# M7101.net
KiCad netlist of a schematic drawn in EAGLE
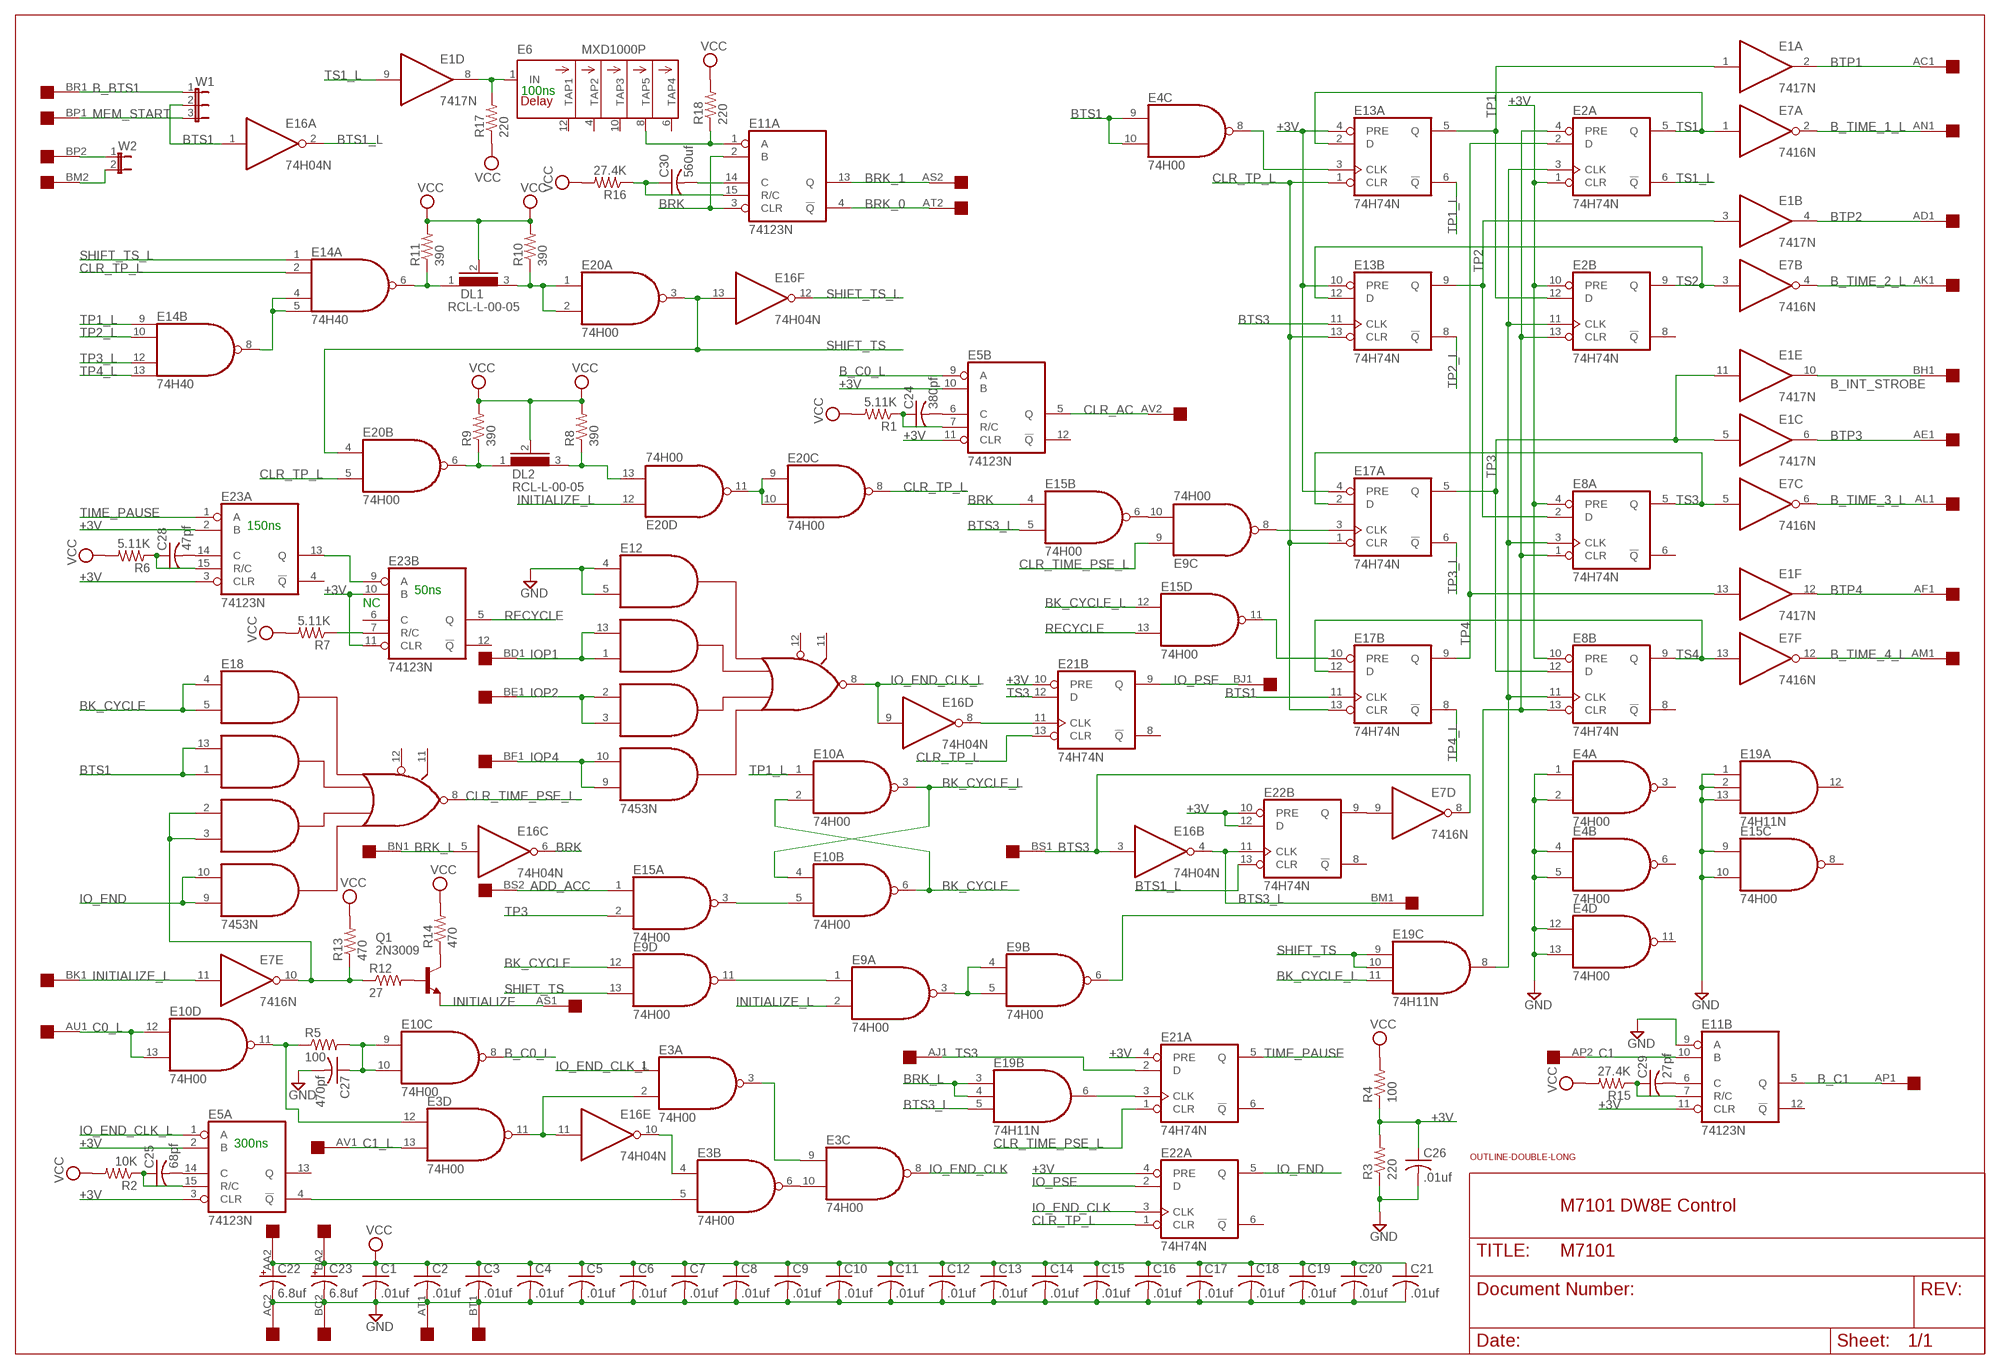
[diagram p0: schematic, sheet 1]

(export (version "E")
  (design (tool "Eeschema 10.0.6"))
  (components
    (comp (ref "C1")
      (value ".01uf")
      (footprint "eagle-import:C050-025X075")
      (libsource (lib "eagle-import") (part "C-US050-025X075"))
    )
    (comp (ref "C2")
      (value ".01uf")
      (footprint "eagle-import:C050-025X075")
      (libsource (lib "eagle-import") (part "C-US050-025X075"))
    )
    (comp (ref "C3")
      (value ".01uf")
      (footprint "eagle-import:C050-025X075")
      (libsource (lib "eagle-import") (part "C-US050-025X075"))
    )
    (comp (ref "C4")
      (value ".01uf")
      (footprint "eagle-import:C050-025X075")
      (libsource (lib "eagle-import") (part "C-US050-025X075"))
    )
    (comp (ref "C5")
      (value ".01uf")
      (footprint "eagle-import:C050-025X075")
      (libsource (lib "eagle-import") (part "C-US050-025X075"))
    )
    (comp (ref "C6")
      (value ".01uf")
      (footprint "eagle-import:C050-025X075")
      (libsource (lib "eagle-import") (part "C-US050-025X075"))
    )
    (comp (ref "C7")
      (value ".01uf")
      (footprint "eagle-import:C050-025X075")
      (libsource (lib "eagle-import") (part "C-US050-025X075"))
    )
    (comp (ref "C8")
      (value ".01uf")
      (footprint "eagle-import:C050-025X075")
      (libsource (lib "eagle-import") (part "C-US050-025X075"))
    )
    (comp (ref "C9")
      (value ".01uf")
      (footprint "eagle-import:C050-025X075")
      (libsource (lib "eagle-import") (part "C-US050-025X075"))
    )
    (comp (ref "C10")
      (value ".01uf")
      (footprint "eagle-import:C050-025X075")
      (libsource (lib "eagle-import") (part "C-US050-025X075"))
    )
    (comp (ref "C11")
      (value ".01uf")
      (footprint "eagle-import:C050-025X075")
      (libsource (lib "eagle-import") (part "C-US050-025X075"))
    )
    (comp (ref "C12")
      (value ".01uf")
      (footprint "eagle-import:C050-025X075")
      (libsource (lib "eagle-import") (part "C-US050-025X075"))
    )
    (comp (ref "C13")
      (value ".01uf")
      (footprint "eagle-import:C050-025X075")
      (libsource (lib "eagle-import") (part "C-US050-025X075"))
    )
    (comp (ref "C14")
      (value ".01uf")
      (footprint "eagle-import:C050-025X075")
      (libsource (lib "eagle-import") (part "C-US050-025X075"))
    )
    (comp (ref "C15")
      (value ".01uf")
      (footprint "eagle-import:C050-025X075")
      (libsource (lib "eagle-import") (part "C-US050-025X075"))
    )
    (comp (ref "C16")
      (value ".01uf")
      (footprint "eagle-import:C050-025X075")
      (libsource (lib "eagle-import") (part "C-US050-025X075"))
    )
    (comp (ref "C17")
      (value ".01uf")
      (footprint "eagle-import:C050-025X075")
      (libsource (lib "eagle-import") (part "C-US050-025X075"))
    )
    (comp (ref "C18")
      (value ".01uf")
      (footprint "eagle-import:C050-025X075")
      (libsource (lib "eagle-import") (part "C-US050-025X075"))
    )
    (comp (ref "C19")
      (value ".01uf")
      (footprint "eagle-import:C050-025X075")
      (libsource (lib "eagle-import") (part "C-US050-025X075"))
    )
    (comp (ref "C20")
      (value ".01uf")
      (footprint "eagle-import:C050-025X075")
      (libsource (lib "eagle-import") (part "C-US050-025X075"))
    )
    (comp (ref "C21")
      (value ".01uf")
      (footprint "eagle-import:C050-025X075")
      (libsource (lib "eagle-import") (part "C-US050-025X075"))
    )
    (comp (ref "C22")
      (value "6.8uf")
      (footprint "eagle-import:E22-6")
      (libsource (lib "eagle-import") (part "CPOL-USE22-6AXIAL"))
    )
    (comp (ref "C23")
      (value "6.8uf")
      (footprint "eagle-import:E22-6")
      (libsource (lib "eagle-import") (part "CPOL-USE22-6AXIAL"))
    )
    (comp (ref "C24")
      (value "380pf")
      (footprint "eagle-import:C050-025X075")
      (libsource (lib "eagle-import") (part "C-US050-025X075"))
    )
    (comp (ref "C25")
      (value "68pf")
      (footprint "eagle-import:C050-025X075")
      (libsource (lib "eagle-import") (part "C-US050-025X075"))
    )
    (comp (ref "C26")
      (value ".01uf")
      (footprint "eagle-import:C050-025X075")
      (libsource (lib "eagle-import") (part "C-US050-025X075"))
    )
    (comp (ref "C27")
      (value "470pf")
      (footprint "eagle-import:C050-025X075")
      (libsource (lib "eagle-import") (part "C-US050-025X075"))
    )
    (comp (ref "C28")
      (value "47pf")
      (footprint "eagle-import:C050-025X075")
      (libsource (lib "eagle-import") (part "C-US050-025X075"))
    )
    (comp (ref "C29")
      (value "27pf")
      (footprint "eagle-import:C050-025X075")
      (libsource (lib "eagle-import") (part "C-US050-025X075"))
    )
    (comp (ref "C30")
      (value "560uf")
      (footprint "eagle-import:C050-025X075")
      (libsource (lib "eagle-import") (part "C-US050-025X075"))
    )
    (comp (ref "DL1")
      (value "RCL-L-00-05")
      (footprint "eagle-import:RCL-L-00-05")
      (libsource (lib "eagle-import") (part "RCL-L-00-05"))
    )
    (comp (ref "DL2")
      (value "RCL-L-00-05")
      (footprint "eagle-import:RCL-L-00-05")
      (libsource (lib "eagle-import") (part "RCL-L-00-05"))
    )
    (comp (ref "E1")
      (value "7417N")
      (footprint "eagle-import:DIL14")
      (libsource (lib "eagle-import") (part "7417N"))
    )
    (comp (ref "E2")
      (value "74H74N")
      (footprint "eagle-import:DIL14")
      (libsource (lib "eagle-import") (part "7474NS"))
    )
    (comp (ref "E3")
      (value "74H00")
      (footprint "eagle-import:DIL14")
      (libsource (lib "eagle-import") (part "7400N"))
    )
    (comp (ref "E4")
      (value "74H00")
      (footprint "eagle-import:DIL14")
      (libsource (lib "eagle-import") (part "7400N"))
    )
    (comp (ref "E5")
      (value "74123N")
      (footprint "eagle-import:DIL16")
      (libsource (lib "eagle-import") (part "74123N"))
    )
    (comp (ref "E6")
      (value "MXD1000P")
      (footprint "eagle-import:DIL14")
      (libsource (lib "eagle-import") (part "MXD1000P"))
    )
    (comp (ref "E7")
      (value "7416N")
      (footprint "eagle-import:DIL14")
      (libsource (lib "eagle-import") (part "7416N"))
    )
    (comp (ref "E8")
      (value "74H74N")
      (footprint "eagle-import:DIL14")
      (libsource (lib "eagle-import") (part "7474NS"))
    )
    (comp (ref "E9")
      (value "74H00")
      (footprint "eagle-import:DIL14")
      (libsource (lib "eagle-import") (part "7400N"))
    )
    (comp (ref "E10")
      (value "74H00")
      (footprint "eagle-import:DIL14")
      (libsource (lib "eagle-import") (part "7400N"))
    )
    (comp (ref "E11")
      (value "74123N")
      (footprint "eagle-import:DIL16")
      (libsource (lib "eagle-import") (part "74123N"))
    )
    (comp (ref "E12")
      (value "7453N")
      (footprint "eagle-import:DIL14")
      (libsource (lib "eagle-import") (part "7453N"))
    )
    (comp (ref "E13")
      (value "74H74N")
      (footprint "eagle-import:DIL14")
      (libsource (lib "eagle-import") (part "7474NS"))
    )
    (comp (ref "E14")
      (value "74H40")
      (footprint "eagle-import:DIL14")
      (libsource (lib "eagle-import") (part "7420NS"))
    )
    (comp (ref "E15")
      (value "74H00")
      (footprint "eagle-import:DIL14")
      (libsource (lib "eagle-import") (part "7400N"))
    )
    (comp (ref "E16")
      (value "74H04N")
      (footprint "eagle-import:DIL14")
      (libsource (lib "eagle-import") (part "7404N"))
    )
    (comp (ref "E17")
      (value "74H74N")
      (footprint "eagle-import:DIL14")
      (libsource (lib "eagle-import") (part "7474NS"))
    )
    (comp (ref "E18")
      (value "7453N")
      (footprint "eagle-import:DIL14")
      (libsource (lib "eagle-import") (part "7453N"))
    )
    (comp (ref "E19")
      (value "74H11N")
      (footprint "eagle-import:DIL14")
      (libsource (lib "eagle-import") (part "7411NS"))
    )
    (comp (ref "E20")
      (value "74H00")
      (footprint "eagle-import:DIL14")
      (libsource (lib "eagle-import") (part "7400N"))
    )
    (comp (ref "E21")
      (value "74H74N")
      (footprint "eagle-import:DIL14")
      (libsource (lib "eagle-import") (part "7474NS"))
    )
    (comp (ref "E22")
      (value "74H74N")
      (footprint "eagle-import:DIL14")
      (libsource (lib "eagle-import") (part "7474NS"))
    )
    (comp (ref "E23")
      (value "74123N")
      (footprint "eagle-import:DIL16")
      (libsource (lib "eagle-import") (part "74123N"))
    )
    (comp (ref "EDGE")
      (value "DOUBLE")
      (footprint "eagle-import:EDGE-CON4")
      (libsource (lib "eagle-import") (part "DOUBLE"))
    )
    (comp (ref "Q1")
      (value "2N3009")
      (footprint "eagle-import:TO18")
      (libsource (lib "eagle-import") (part "2N2222"))
    )
    (comp (ref "R1")
      (value "5.11K")
      (footprint "eagle-import:0207_10")
      (libsource (lib "eagle-import") (part "R-US_0207/10"))
    )
    (comp (ref "R2")
      (value "10K")
      (footprint "eagle-import:0207_10")
      (libsource (lib "eagle-import") (part "R-US_0207/10"))
    )
    (comp (ref "R3")
      (value "220")
      (footprint "eagle-import:0207_10")
      (libsource (lib "eagle-import") (part "R-US_0207/10"))
    )
    (comp (ref "R4")
      (value "100")
      (footprint "eagle-import:0207_10")
      (libsource (lib "eagle-import") (part "R-US_0207/10"))
    )
    (comp (ref "R5")
      (value "100")
      (footprint "eagle-import:0207_10")
      (libsource (lib "eagle-import") (part "R-US_0207/10"))
    )
    (comp (ref "R6")
      (value "5.11K")
      (footprint "eagle-import:0207_10")
      (libsource (lib "eagle-import") (part "R-US_0207/10"))
    )
    (comp (ref "R7")
      (value "5.11K")
      (footprint "eagle-import:0207_10")
      (libsource (lib "eagle-import") (part "R-US_0207/10"))
    )
    (comp (ref "R8")
      (value "390")
      (footprint "eagle-import:0207_10")
      (libsource (lib "eagle-import") (part "R-US_0207/10"))
    )
    (comp (ref "R9")
      (value "390")
      (footprint "eagle-import:0207_10")
      (libsource (lib "eagle-import") (part "R-US_0207/10"))
    )
    (comp (ref "R10")
      (value "390")
      (footprint "eagle-import:0207_10")
      (libsource (lib "eagle-import") (part "R-US_0207/10"))
    )
    (comp (ref "R11")
      (value "390")
      (footprint "eagle-import:0207_10")
      (libsource (lib "eagle-import") (part "R-US_0207/10"))
    )
    (comp (ref "R12")
      (value "27")
      (footprint "eagle-import:0207_10")
      (libsource (lib "eagle-import") (part "R-US_0207/10"))
    )
    (comp (ref "R13")
      (value "470")
      (footprint "eagle-import:0207_10")
      (libsource (lib "eagle-import") (part "R-US_0207/10"))
    )
    (comp (ref "R14")
      (value "470")
      (footprint "eagle-import:0207_10")
      (libsource (lib "eagle-import") (part "R-US_0207/10"))
    )
    (comp (ref "R15")
      (value "27.4K")
      (footprint "eagle-import:0207_10")
      (libsource (lib "eagle-import") (part "R-US_0207/10"))
    )
    (comp (ref "R16")
      (value "27.4K")
      (footprint "eagle-import:0207_10")
      (libsource (lib "eagle-import") (part "R-US_0207/10"))
    )
    (comp (ref "R17")
      (value "220")
      (footprint "eagle-import:0207_10")
      (libsource (lib "eagle-import") (part "R-US_0207/10"))
    )
    (comp (ref "R18")
      (value "220")
      (footprint "eagle-import:0207_10")
      (libsource (lib "eagle-import") (part "R-US_0207/10"))
    )
    (comp (ref "U$1")
      (value "OUTLINE-DOUBLE-LONG")
      (footprint "eagle-import:DOUBLE-LONG")
      (libsource (lib "eagle-import") (part "OUTLINE-DOUBLE-LONG"))
    )
    (comp (ref "W1")
      (value "JP2E")
      (footprint "eagle-import:JP2")
      (libsource (lib "eagle-import") (part "JP2E"))
    )
    (comp (ref "W2")
      (value "JP1E")
      (footprint "eagle-import:JP1")
      (libsource (lib "eagle-import") (part "JP1E"))
    )
  )
  (nets
    (net (code "1") (name "/+3V") (class "Default")
      (node (ref "C26") (pin "1") (pinfunction "1_1") (pintype "passive"))
      (node (ref "E11") (pin "11") (pinfunction "CLR_11") (pintype "input"))
      (node (ref "E13") (pin "10") (pinfunction "PRE_10") (pintype "input"))
      (node (ref "E13") (pin "4") (pinfunction "PRE_4") (pintype "input"))
      (node (ref "E17") (pin "4") (pinfunction "PRE_4") (pintype "input"))
      (node (ref "E2") (pin "1") (pinfunction "CLR_1") (pintype "input"))
      (node (ref "E2") (pin "10") (pinfunction "PRE_10") (pintype "input"))
      (node (ref "E21") (pin "10") (pinfunction "PRE_10") (pintype "input"))
      (node (ref "E21") (pin "4") (pinfunction "PRE_4") (pintype "input"))
      (node (ref "E22") (pin "10") (pinfunction "PRE_10") (pintype "input"))
      (node (ref "E22") (pin "12") (pinfunction "D_12") (pintype "input"))
      (node (ref "E22") (pin "4") (pinfunction "PRE_4") (pintype "input"))
      (node (ref "E23") (pin "10") (pinfunction "B_10") (pintype "input"))
      (node (ref "E23") (pin "11") (pinfunction "CLR_11") (pintype "input"))
      (node (ref "E23") (pin "2") (pinfunction "B_2") (pintype "input"))
      (node (ref "E23") (pin "3") (pinfunction "CLR_3") (pintype "input"))
      (node (ref "E5") (pin "10") (pinfunction "B_10") (pintype "input"))
      (node (ref "E5") (pin "11") (pinfunction "CLR_11") (pintype "input"))
      (node (ref "E5") (pin "2") (pinfunction "B_2") (pintype "input"))
      (node (ref "E5") (pin "3") (pinfunction "CLR_3") (pintype "input"))
      (node (ref "E8") (pin "10") (pinfunction "PRE_10") (pintype "input"))
      (node (ref "E8") (pin "4") (pinfunction "PRE_4") (pintype "input"))
      (node (ref "R3") (pin "2") (pinfunction "2_2") (pintype "passive"))
      (node (ref "R4") (pin "1") (pinfunction "1_1") (pintype "passive"))
    )
    (net (code "2") (name "/ADD_ACC") (class "Default")
      (node (ref "E15") (pin "1") (pinfunction "I0_1") (pintype "input"))
      (node (ref "EDGE") (pin "BS2") (pinfunction "1_BS2") (pintype "bidirectional"))
    )
    (net (code "3") (name "/BK_CYCLE") (class "Default")
      (node (ref "E10") (pin "2") (pinfunction "I1_2") (pintype "input"))
      (node (ref "E10") (pin "6") (pinfunction "O_6") (pintype "output"))
      (node (ref "E18") (pin "4") (pinfunction "I1_4") (pintype "input"))
      (node (ref "E18") (pin "5") (pinfunction "I2_5") (pintype "input"))
      (node (ref "E9") (pin "12") (pinfunction "I0_12") (pintype "input"))
    )
    (net (code "4") (name "/BK_CYCLE_L") (class "Default")
      (node (ref "E10") (pin "3") (pinfunction "O_3") (pintype "output"))
      (node (ref "E10") (pin "4") (pinfunction "I0_4") (pintype "input"))
      (node (ref "E15") (pin "12") (pinfunction "I0_12") (pintype "input"))
      (node (ref "E19") (pin "11") (pinfunction "I2_11") (pintype "input"))
    )
    (net (code "5") (name "/BRK") (class "Default")
      (node (ref "E11") (pin "2") (pinfunction "B_2") (pintype "input"))
      (node (ref "E11") (pin "3") (pinfunction "CLR_3") (pintype "input"))
      (node (ref "E15") (pin "4") (pinfunction "I0_4") (pintype "input"))
      (node (ref "E16") (pin "6") (pinfunction "O_6") (pintype "output"))
    )
    (net (code "6") (name "/BRK_0") (class "Default")
      (node (ref "E11") (pin "4") (pinfunction "~{Q}_4") (pintype "output"))
      (node (ref "EDGE") (pin "AT2") (pinfunction "1_AT2") (pintype "bidirectional"))
    )
    (net (code "7") (name "/BRK_1") (class "Default")
      (node (ref "E11") (pin "13") (pinfunction "Q_13") (pintype "output"))
      (node (ref "EDGE") (pin "AS2") (pinfunction "1_AS2") (pintype "bidirectional"))
    )
    (net (code "8") (name "/BRK_L") (class "Default")
      (node (ref "E16") (pin "5") (pinfunction "I_5") (pintype "input"))
      (node (ref "E19") (pin "3") (pinfunction "I0_3") (pintype "input"))
      (node (ref "E19") (pin "4") (pinfunction "I1_4") (pintype "input"))
      (node (ref "EDGE") (pin "BN1") (pinfunction "1_BN1") (pintype "bidirectional"))
    )
    (net (code "9") (name "/BTP1") (class "Default")
      (node (ref "E1") (pin "2") (pinfunction "O_2") (pintype "open_collector"))
      (node (ref "EDGE") (pin "AC1") (pinfunction "1_AC1") (pintype "bidirectional"))
    )
    (net (code "10") (name "/BTP2") (class "Default")
      (node (ref "E1") (pin "4") (pinfunction "O_4") (pintype "open_collector"))
      (node (ref "EDGE") (pin "AD1") (pinfunction "1_AD1") (pintype "bidirectional"))
    )
    (net (code "11") (name "/BTP3") (class "Default")
      (node (ref "E1") (pin "6") (pinfunction "O_6") (pintype "open_collector"))
      (node (ref "EDGE") (pin "AE1") (pinfunction "1_AE1") (pintype "bidirectional"))
    )
    (net (code "12") (name "/BTP4") (class "Default")
      (node (ref "E1") (pin "12") (pinfunction "O_12") (pintype "open_collector"))
      (node (ref "EDGE") (pin "AF1") (pinfunction "1_AF1") (pintype "bidirectional"))
    )
    (net (code "13") (name "/BTS1") (class "Default")
      (node (ref "E16") (pin "1") (pinfunction "I_1") (pintype "input"))
      (node (ref "E17") (pin "11") (pinfunction "CLK_11") (pintype "input"))
      (node (ref "E18") (pin "1") (pinfunction "I4_1") (pintype "input"))
      (node (ref "E18") (pin "13") (pinfunction "I3_13") (pintype "input"))
      (node (ref "E4") (pin "10") (pinfunction "I1_10") (pintype "input"))
      (node (ref "E4") (pin "9") (pinfunction "I0_9") (pintype "input"))
      (node (ref "W1") (pin "2") (pinfunction "2_2") (pintype "passive"))
    )
    (net (code "14") (name "/BTS1_L") (class "Default")
      (node (ref "E16") (pin "2") (pinfunction "O_2") (pintype "output"))
      (node (ref "E22") (pin "13") (pinfunction "CLR_13") (pintype "input"))
    )
    (net (code "15") (name "/BTS3") (class "Default")
      (node (ref "E13") (pin "11") (pinfunction "CLK_11") (pintype "input"))
      (node (ref "E16") (pin "3") (pinfunction "I_3") (pintype "input"))
      (node (ref "E7") (pin "8") (pinfunction "O_8") (pintype "open_collector"))
      (node (ref "EDGE") (pin "BS1") (pinfunction "1_BS1") (pintype "bidirectional"))
    )
    (net (code "16") (name "/BTS3_L") (class "Default")
      (node (ref "E15") (pin "5") (pinfunction "I1_5") (pintype "input"))
      (node (ref "E16") (pin "4") (pinfunction "O_4") (pintype "output"))
      (node (ref "E19") (pin "5") (pinfunction "I2_5") (pintype "input"))
      (node (ref "E22") (pin "11") (pinfunction "CLK_11") (pintype "input"))
      (node (ref "EDGE") (pin "BM1") (pinfunction "1_BM1") (pintype "bidirectional"))
    )
    (net (code "17") (name "/B_BTS1") (class "Default")
      (node (ref "EDGE") (pin "BR1") (pinfunction "1_BR1") (pintype "bidirectional"))
      (node (ref "W1") (pin "1") (pinfunction "1_1") (pintype "passive"))
    )
    (net (code "18") (name "/B_C0_L") (class "Default")
      (node (ref "E10") (pin "8") (pinfunction "O_8") (pintype "output"))
      (node (ref "E5") (pin "9") (pinfunction "A_9") (pintype "input"))
    )
    (net (code "19") (name "/B_C1") (class "Default")
      (node (ref "E11") (pin "5") (pinfunction "Q_5") (pintype "output"))
      (node (ref "EDGE") (pin "AP1") (pinfunction "1_AP1") (pintype "bidirectional"))
    )
    (net (code "20") (name "/B_INT_STROBE") (class "Default")
      (node (ref "E1") (pin "10") (pinfunction "O_10") (pintype "open_collector"))
      (node (ref "EDGE") (pin "BH1") (pinfunction "1_BH1") (pintype "bidirectional"))
    )
    (net (code "21") (name "/B_TIME_1_L") (class "Default")
      (node (ref "E7") (pin "2") (pinfunction "O_2") (pintype "open_collector"))
      (node (ref "EDGE") (pin "AN1") (pinfunction "1_AN1") (pintype "bidirectional"))
    )
    (net (code "22") (name "/B_TIME_2_L") (class "Default")
      (node (ref "E7") (pin "4") (pinfunction "O_4") (pintype "open_collector"))
      (node (ref "EDGE") (pin "AK1") (pinfunction "1_AK1") (pintype "bidirectional"))
    )
    (net (code "23") (name "/B_TIME_3_L") (class "Default")
      (node (ref "E7") (pin "6") (pinfunction "O_6") (pintype "open_collector"))
      (node (ref "EDGE") (pin "AL1") (pinfunction "1_AL1") (pintype "bidirectional"))
    )
    (net (code "24") (name "/B_TIME_4_L") (class "Default")
      (node (ref "E7") (pin "12") (pinfunction "O_12") (pintype "open_collector"))
      (node (ref "EDGE") (pin "AM1") (pinfunction "1_AM1") (pintype "bidirectional"))
    )
    (net (code "25") (name "/C0_L") (class "Default")
      (node (ref "E10") (pin "12") (pinfunction "I0_12") (pintype "input"))
      (node (ref "E10") (pin "13") (pinfunction "I1_13") (pintype "input"))
      (node (ref "EDGE") (pin "AU1") (pinfunction "1_AU1") (pintype "bidirectional"))
    )
    (net (code "26") (name "/C1") (class "Default")
      (node (ref "E11") (pin "10") (pinfunction "B_10") (pintype "input"))
      (node (ref "EDGE") (pin "AP2") (pinfunction "1_AP2") (pintype "bidirectional"))
    )
    (net (code "27") (name "/C1_L") (class "Default")
      (node (ref "E3") (pin "13") (pinfunction "I1_13") (pintype "input"))
      (node (ref "EDGE") (pin "AV1") (pinfunction "1_AV1") (pintype "bidirectional"))
    )
    (net (code "28") (name "/CLR_AC") (class "Default")
      (node (ref "E5") (pin "5") (pinfunction "Q_5") (pintype "output"))
      (node (ref "EDGE") (pin "AV2") (pinfunction "1_AV2") (pintype "bidirectional"))
    )
    (net (code "29") (name "/CLR_TIME_PSE_L") (class "Default")
      (node (ref "E18") (pin "8") (pinfunction "O_8") (pintype "output"))
      (node (ref "E21") (pin "1") (pinfunction "CLR_1") (pintype "input"))
      (node (ref "E9") (pin "9") (pinfunction "I0_9") (pintype "input"))
    )
    (net (code "30") (name "/CLR_TP_L") (class "Default")
      (node (ref "E13") (pin "1") (pinfunction "CLR_1") (pintype "input"))
      (node (ref "E13") (pin "13") (pinfunction "CLR_13") (pintype "input"))
      (node (ref "E14") (pin "2") (pinfunction "I1_2") (pintype "input"))
      (node (ref "E17") (pin "1") (pinfunction "CLR_1") (pintype "input"))
      (node (ref "E17") (pin "13") (pinfunction "CLR_13") (pintype "input"))
      (node (ref "E20") (pin "5") (pinfunction "I1_5") (pintype "input"))
      (node (ref "E20") (pin "8") (pinfunction "O_8") (pintype "output"))
      (node (ref "E21") (pin "13") (pinfunction "CLR_13") (pintype "input"))
      (node (ref "E22") (pin "1") (pinfunction "CLR_1") (pintype "input"))
    )
    (net (code "31") (name "/INITIALIZE") (class "Default")
      (node (ref "EDGE") (pin "AS1") (pinfunction "1_AS1") (pintype "bidirectional"))
      (node (ref "Q1") (pin "1") (pinfunction "E_1") (pintype "passive"))
    )
    (net (code "32") (name "/INITIALIZE_L") (class "Default")
      (node (ref "E20") (pin "12") (pinfunction "I0_12") (pintype "input"))
      (node (ref "E7") (pin "11") (pinfunction "I_11") (pintype "input"))
      (node (ref "E9") (pin "2") (pinfunction "I1_2") (pintype "input"))
      (node (ref "EDGE") (pin "BK1") (pinfunction "1_BK1") (pintype "bidirectional"))
    )
    (net (code "33") (name "/IOP1") (class "Default")
      (node (ref "E12") (pin "1") (pinfunction "I4_1") (pintype "input"))
      (node (ref "E12") (pin "13") (pinfunction "I3_13") (pintype "input"))
      (node (ref "EDGE") (pin "BD1") (pinfunction "1_BD1") (pintype "bidirectional"))
    )
    (net (code "34") (name "/IOP2") (class "Default")
      (node (ref "E12") (pin "2") (pinfunction "I5_2") (pintype "input"))
      (node (ref "E12") (pin "3") (pinfunction "I6_3") (pintype "input"))
      (node (ref "EDGE") (pin "BE1") (pinfunction "1_BE1") (pintype "bidirectional"))
    )
    (net (code "35") (name "/IOP4") (class "Default")
      (node (ref "E12") (pin "10") (pinfunction "I7_10") (pintype "input"))
      (node (ref "E12") (pin "9") (pinfunction "I8_9") (pintype "input"))
      (node (ref "EDGE") (pin "BF1") (pinfunction "1_BF1") (pintype "bidirectional"))
    )
    (net (code "36") (name "/IO_END") (class "Default")
      (node (ref "E18") (pin "10") (pinfunction "I7_10") (pintype "input"))
      (node (ref "E18") (pin "9") (pinfunction "I8_9") (pintype "input"))
      (node (ref "E22") (pin "5") (pinfunction "Q_5") (pintype "output"))
    )
    (net (code "37") (name "/IO_END_CLK") (class "Default")
      (node (ref "E22") (pin "3") (pinfunction "CLK_3") (pintype "input"))
      (node (ref "E3") (pin "8") (pinfunction "O_8") (pintype "output"))
    )
    (net (code "38") (name "/IO_END_CLK_L") (class "Default")
      (node (ref "E12") (pin "8") (pinfunction "O_8") (pintype "output"))
      (node (ref "E16") (pin "9") (pinfunction "I_9") (pintype "input"))
      (node (ref "E3") (pin "1") (pinfunction "I0_1") (pintype "input"))
      (node (ref "E5") (pin "1") (pinfunction "A_1") (pintype "input"))
    )
    (net (code "39") (name "/IO_PSE") (class "Default")
      (node (ref "E21") (pin "9") (pinfunction "Q_9") (pintype "output"))
      (node (ref "E22") (pin "2") (pinfunction "D_2") (pintype "input"))
      (node (ref "EDGE") (pin "BJ1") (pinfunction "1_BJ1") (pintype "bidirectional"))
    )
    (net (code "40") (name "/MEM_START") (class "Default")
      (node (ref "EDGE") (pin "BP1") (pinfunction "1_BP1") (pintype "bidirectional"))
      (node (ref "W1") (pin "3") (pinfunction "3_3") (pintype "passive"))
    )
    (net (code "41") (name "/RECYCLE") (class "Default")
      (node (ref "E15") (pin "13") (pinfunction "I1_13") (pintype "input"))
      (node (ref "E23") (pin "5") (pinfunction "Q_5") (pintype "output"))
    )
    (net (code "42") (name "/SHIFT_TS") (class "Default")
      (node (ref "E16") (pin "13") (pinfunction "I_13") (pintype "input"))
      (node (ref "E19") (pin "10") (pinfunction "I1_10") (pintype "input"))
      (node (ref "E19") (pin "9") (pinfunction "I0_9") (pintype "input"))
      (node (ref "E20") (pin "3") (pinfunction "O_3") (pintype "output"))
      (node (ref "E20") (pin "4") (pinfunction "I0_4") (pintype "input"))
      (node (ref "E9") (pin "13") (pinfunction "I1_13") (pintype "input"))
    )
    (net (code "43") (name "/SHIFT_TS_L") (class "Default")
      (node (ref "E14") (pin "1") (pinfunction "I0_1") (pintype "input"))
      (node (ref "E16") (pin "12") (pinfunction "O_12") (pintype "output"))
    )
    (net (code "44") (name "/TIME_PAUSE") (class "Default")
      (node (ref "E21") (pin "5") (pinfunction "Q_5") (pintype "output"))
      (node (ref "E23") (pin "1") (pinfunction "A_1") (pintype "input"))
    )
    (net (code "45") (name "/TP1") (class "Default")
      (node (ref "E1") (pin "1") (pinfunction "I_1") (pintype "input"))
      (node (ref "E13") (pin "5") (pinfunction "Q_5") (pintype "output"))
      (node (ref "E2") (pin "12") (pinfunction "D_12") (pintype "input"))
    )
    (net (code "46") (name "/TP1_L") (class "Default")
      (node (ref "E10") (pin "1") (pinfunction "I0_1") (pintype "input"))
      (node (ref "E13") (pin "6") (pinfunction "~{Q}_6") (pintype "output"))
      (node (ref "E14") (pin "9") (pinfunction "I0_9") (pintype "input"))
    )
    (net (code "47") (name "/TP2") (class "Default")
      (node (ref "E1") (pin "3") (pinfunction "I_3") (pintype "input"))
      (node (ref "E13") (pin "9") (pinfunction "Q_9") (pintype "output"))
      (node (ref "E8") (pin "2") (pinfunction "D_2") (pintype "input"))
    )
    (net (code "48") (name "/TP2_L") (class "Default")
      (node (ref "E13") (pin "8") (pinfunction "~{Q}_8") (pintype "output"))
      (node (ref "E14") (pin "10") (pinfunction "I1_10") (pintype "input"))
    )
    (net (code "49") (name "/TP3") (class "Default")
      (node (ref "E1") (pin "11") (pinfunction "I_11") (pintype "input"))
      (node (ref "E1") (pin "5") (pinfunction "I_5") (pintype "input"))
      (node (ref "E15") (pin "2") (pinfunction "I1_2") (pintype "input"))
      (node (ref "E17") (pin "5") (pinfunction "Q_5") (pintype "output"))
      (node (ref "E8") (pin "12") (pinfunction "D_12") (pintype "input"))
    )
    (net (code "50") (name "/TP3_L") (class "Default")
      (node (ref "E14") (pin "12") (pinfunction "I2_12") (pintype "input"))
      (node (ref "E17") (pin "6") (pinfunction "~{Q}_6") (pintype "output"))
    )
    (net (code "51") (name "/TP4") (class "Default")
      (node (ref "E1") (pin "13") (pinfunction "I_13") (pintype "input"))
      (node (ref "E17") (pin "9") (pinfunction "Q_9") (pintype "output"))
      (node (ref "E2") (pin "2") (pinfunction "D_2") (pintype "input"))
    )
    (net (code "52") (name "/TP4_L") (class "Default")
      (node (ref "E14") (pin "13") (pinfunction "I3_13") (pintype "input"))
      (node (ref "E17") (pin "8") (pinfunction "~{Q}_8") (pintype "output"))
    )
    (net (code "53") (name "/TS1") (class "Default")
      (node (ref "E13") (pin "2") (pinfunction "D_2") (pintype "input"))
      (node (ref "E2") (pin "5") (pinfunction "Q_5") (pintype "output"))
      (node (ref "E7") (pin "1") (pinfunction "I_1") (pintype "input"))
    )
    (net (code "54") (name "/TS1_L") (class "Default")
      (node (ref "E1") (pin "9") (pinfunction "I_9") (pintype "input"))
      (node (ref "E2") (pin "6") (pinfunction "~{Q}_6") (pintype "output"))
    )
    (net (code "55") (name "/TS2") (class "Default")
      (node (ref "E13") (pin "12") (pinfunction "D_12") (pintype "input"))
      (node (ref "E2") (pin "9") (pinfunction "Q_9") (pintype "output"))
      (node (ref "E7") (pin "3") (pinfunction "I_3") (pintype "input"))
    )
    (net (code "56") (name "/TS3") (class "Default")
      (node (ref "E17") (pin "2") (pinfunction "D_2") (pintype "input"))
      (node (ref "E21") (pin "12") (pinfunction "D_12") (pintype "input"))
      (node (ref "E21") (pin "2") (pinfunction "D_2") (pintype "input"))
      (node (ref "E7") (pin "5") (pinfunction "I_5") (pintype "input"))
      (node (ref "E8") (pin "5") (pinfunction "Q_5") (pintype "output"))
      (node (ref "EDGE") (pin "AJ1") (pinfunction "1_AJ1") (pintype "bidirectional"))
    )
    (net (code "57") (name "/TS4") (class "Default")
      (node (ref "E17") (pin "12") (pinfunction "D_12") (pintype "input"))
      (node (ref "E7") (pin "13") (pinfunction "I_13") (pintype "input"))
      (node (ref "E8") (pin "9") (pinfunction "Q_9") (pintype "output"))
    )
    (net (code "58") (name "GND") (class "Default")
      (node (ref "C1") (pin "2") (pinfunction "2_2") (pintype "passive"))
      (node (ref "C10") (pin "2") (pinfunction "2_2") (pintype "passive"))
      (node (ref "C11") (pin "2") (pinfunction "2_2") (pintype "passive"))
      (node (ref "C12") (pin "2") (pinfunction "2_2") (pintype "passive"))
      (node (ref "C13") (pin "2") (pinfunction "2_2") (pintype "passive"))
      (node (ref "C14") (pin "2") (pinfunction "2_2") (pintype "passive"))
      (node (ref "C15") (pin "2") (pinfunction "2_2") (pintype "passive"))
      (node (ref "C16") (pin "2") (pinfunction "2_2") (pintype "passive"))
      (node (ref "C17") (pin "2") (pinfunction "2_2") (pintype "passive"))
      (node (ref "C18") (pin "2") (pinfunction "2_2") (pintype "passive"))
      (node (ref "C19") (pin "2") (pinfunction "2_2") (pintype "passive"))
      (node (ref "C2") (pin "2") (pinfunction "2_2") (pintype "passive"))
      (node (ref "C20") (pin "2") (pinfunction "2_2") (pintype "passive"))
      (node (ref "C21") (pin "2") (pinfunction "2_2") (pintype "passive"))
      (node (ref "C22") (pin "-") (pinfunction "-_-") (pintype "passive"))
      (node (ref "C23") (pin "-") (pinfunction "-_-") (pintype "passive"))
      (node (ref "C26") (pin "2") (pinfunction "2_2") (pintype "passive"))
      (node (ref "C27") (pin "2") (pinfunction "2_2") (pintype "passive"))
      (node (ref "C3") (pin "2") (pinfunction "2_2") (pintype "passive"))
      (node (ref "C4") (pin "2") (pinfunction "2_2") (pintype "passive"))
      (node (ref "C5") (pin "2") (pinfunction "2_2") (pintype "passive"))
      (node (ref "C6") (pin "2") (pinfunction "2_2") (pintype "passive"))
      (node (ref "C7") (pin "2") (pinfunction "2_2") (pintype "passive"))
      (node (ref "C8") (pin "2") (pinfunction "2_2") (pintype "passive"))
      (node (ref "C9") (pin "2") (pinfunction "2_2") (pintype "passive"))
      (node (ref "E11") (pin "9") (pinfunction "A_9") (pintype "input"))
      (node (ref "E12") (pin "4") (pinfunction "I1_4") (pintype "input"))
      (node (ref "E12") (pin "5") (pinfunction "I2_5") (pintype "input"))
      (node (ref "E15") (pin "10") (pinfunction "I1_10") (pintype "input"))
      (node (ref "E15") (pin "9") (pinfunction "I0_9") (pintype "input"))
      (node (ref "E19") (pin "1") (pinfunction "I0_1") (pintype "input"))
      (node (ref "E19") (pin "13") (pinfunction "I2_13") (pintype "input"))
      (node (ref "E19") (pin "2") (pinfunction "I1_2") (pintype "input"))
      (node (ref "E4") (pin "1") (pinfunction "I0_1") (pintype "input"))
      (node (ref "E4") (pin "12") (pinfunction "I0_12") (pintype "input"))
      (node (ref "E4") (pin "13") (pinfunction "I1_13") (pintype "input"))
      (node (ref "E4") (pin "2") (pinfunction "I1_2") (pintype "input"))
      (node (ref "E4") (pin "4") (pinfunction "I0_4") (pintype "input"))
      (node (ref "E4") (pin "5") (pinfunction "I1_5") (pintype "input"))
      (node (ref "EDGE") (pin "AC2") (pinfunction "1_AC2") (pintype "bidirectional"))
      (node (ref "EDGE") (pin "AT1") (pinfunction "1_AT1") (pintype "bidirectional"))
      (node (ref "EDGE") (pin "BC2") (pinfunction "1_BC2") (pintype "bidirectional"))
      (node (ref "EDGE") (pin "BT1") (pinfunction "1_BT1") (pintype "bidirectional"))
      (node (ref "R3") (pin "1") (pinfunction "1_1") (pintype "passive"))
    )
    (net (code "59") (name "Net-(E1D-O)") (class "Default")
      (node (ref "E1") (pin "8") (pinfunction "O_8") (pintype "open_collector"))
      (node (ref "E6") (pin "1") (pinfunction "IN_1") (pintype "input"))
      (node (ref "R17") (pin "2") (pinfunction "2_2") (pintype "passive"))
    )
    (net (code "60") (name "Net-(E2A-PRE)") (class "Default")
      (node (ref "E2") (pin "13") (pinfunction "CLR_13") (pintype "input"))
      (node (ref "E2") (pin "4") (pinfunction "PRE_4") (pintype "input"))
      (node (ref "E8") (pin "1") (pinfunction "CLR_1") (pintype "input"))
      (node (ref "E8") (pin "13") (pinfunction "CLR_13") (pintype "input"))
      (node (ref "E9") (pin "6") (pinfunction "O_6") (pintype "output"))
    )
    (net (code "61") (name "Net-(E3A-O)") (class "Default")
      (node (ref "E3") (pin "3") (pinfunction "O_3") (pintype "output"))
      (node (ref "E3") (pin "9") (pinfunction "I0_9") (pintype "input"))
    )
    (net (code "62") (name "Net-(E3B-I1)") (class "Default")
      (node (ref "E3") (pin "5") (pinfunction "I1_5") (pintype "input"))
      (node (ref "E5") (pin "4") (pinfunction "~{Q}_4") (pintype "output"))
    )
    (net (code "63") (name "Net-(E3B-O)") (class "Default")
      (node (ref "E3") (pin "10") (pinfunction "I1_10") (pintype "input"))
      (node (ref "E3") (pin "6") (pinfunction "O_6") (pintype "output"))
    )
    (net (code "64") (name "Net-(E5A-C)") (class "Default")
      (node (ref "C25") (pin "2") (pinfunction "2_2") (pintype "passive"))
      (node (ref "E5") (pin "14") (pinfunction "C_14") (pintype "input"))
    )
    (net (code "65") (name "Net-(E5A-R{slash}C)") (class "Default")
      (node (ref "C25") (pin "1") (pinfunction "1_1") (pintype "passive"))
      (node (ref "E5") (pin "15") (pinfunction "R/C_15") (pintype "input"))
      (node (ref "R2") (pin "1") (pinfunction "1_1") (pintype "passive"))
    )
    (net (code "66") (name "Net-(E5B-C)") (class "Default")
      (node (ref "C24") (pin "2") (pinfunction "2_2") (pintype "passive"))
      (node (ref "E5") (pin "6") (pinfunction "C_6") (pintype "input"))
    )
    (net (code "67") (name "Net-(E5B-R{slash}C)") (class "Default")
      (node (ref "C24") (pin "1") (pinfunction "1_1") (pintype "passive"))
      (node (ref "E5") (pin "7") (pinfunction "R/C_7") (pintype "input"))
      (node (ref "R1") (pin "1") (pinfunction "1_1") (pintype "passive"))
    )
    (net (code "68") (name "Net-(E9A-I0)") (class "Default")
      (node (ref "E9") (pin "1") (pinfunction "I0_1") (pintype "input"))
      (node (ref "E9") (pin "11") (pinfunction "O_11") (pintype "output"))
    )
    (net (code "69") (name "Net-(E9A-O)") (class "Default")
      (node (ref "E9") (pin "3") (pinfunction "O_3") (pintype "output"))
      (node (ref "E9") (pin "4") (pinfunction "I0_4") (pintype "input"))
      (node (ref "E9") (pin "5") (pinfunction "I1_5") (pintype "input"))
    )
    (net (code "70") (name "Net-(E10B-I1)") (class "Default")
      (node (ref "E10") (pin "5") (pinfunction "I1_5") (pintype "input"))
      (node (ref "E15") (pin "3") (pinfunction "O_3") (pintype "output"))
    )
    (net (code "71") (name "Net-(E10C-I0)") (class "Default")
      (node (ref "C27") (pin "1") (pinfunction "1_1") (pintype "passive"))
      (node (ref "E10") (pin "10") (pinfunction "I1_10") (pintype "input"))
      (node (ref "E10") (pin "9") (pinfunction "I0_9") (pintype "input"))
      (node (ref "R5") (pin "2") (pinfunction "2_2") (pintype "passive"))
    )
    (net (code "72") (name "Net-(E10D-O)") (class "Default")
      (node (ref "E10") (pin "11") (pinfunction "O_11") (pintype "output"))
      (node (ref "E3") (pin "12") (pinfunction "I0_12") (pintype "input"))
      (node (ref "R5") (pin "1") (pinfunction "1_1") (pintype "passive"))
    )
    (net (code "73") (name "Net-(E11A-A)") (class "Default")
      (node (ref "E11") (pin "1") (pinfunction "A_1") (pintype "input"))
      (node (ref "E6") (pin "8") (pinfunction "TAP5_8") (pintype "output"))
      (node (ref "R18") (pin "1") (pinfunction "1_1") (pintype "passive"))
    )
    (net (code "74") (name "Net-(E11A-C)") (class "Default")
      (node (ref "C30") (pin "2") (pinfunction "2_2") (pintype "passive"))
      (node (ref "E11") (pin "14") (pinfunction "C_14") (pintype "input"))
    )
    (net (code "75") (name "Net-(E11A-R{slash}C)") (class "Default")
      (node (ref "C30") (pin "1") (pinfunction "1_1") (pintype "passive"))
      (node (ref "E11") (pin "15") (pinfunction "R/C_15") (pintype "input"))
      (node (ref "R16") (pin "1") (pinfunction "1_1") (pintype "passive"))
    )
    (net (code "76") (name "Net-(E11B-C)") (class "Default")
      (node (ref "C29") (pin "2") (pinfunction "2_2") (pintype "passive"))
      (node (ref "E11") (pin "6") (pinfunction "C_6") (pintype "input"))
    )
    (net (code "77") (name "Net-(E11B-R{slash}C)") (class "Default")
      (node (ref "C29") (pin "1") (pinfunction "1_1") (pintype "passive"))
      (node (ref "E11") (pin "7") (pinfunction "R/C_7") (pintype "input"))
      (node (ref "R15") (pin "1") (pinfunction "1_1") (pintype "passive"))
    )
    (net (code "78") (name "Net-(E13A-CLK)") (class "Default")
      (node (ref "E13") (pin "3") (pinfunction "CLK_3") (pintype "input"))
      (node (ref "E4") (pin "8") (pinfunction "O_8") (pintype "output"))
    )
    (net (code "79") (name "Net-(E14A-I2)") (class "Default")
      (node (ref "E14") (pin "4") (pinfunction "I2_4") (pintype "input"))
      (node (ref "E14") (pin "5") (pinfunction "I3_5") (pintype "input"))
      (node (ref "E14") (pin "8") (pinfunction "O_8") (pintype "output"))
    )
    (net (code "80") (name "Net-(E14A-O)") (class "Default")
      (node (ref "DL1") (pin "1") (pinfunction "1_1") (pintype "passive"))
      (node (ref "E14") (pin "6") (pinfunction "O_6") (pintype "output"))
      (node (ref "R11") (pin "1") (pinfunction "1_1") (pintype "passive"))
    )
    (net (code "81") (name "Net-(E15B-O)") (class "Default")
      (node (ref "E15") (pin "6") (pinfunction "O_6") (pintype "output"))
      (node (ref "E9") (pin "10") (pinfunction "I1_10") (pintype "input"))
    )
    (net (code "82") (name "Net-(E15D-O)") (class "Default")
      (node (ref "E15") (pin "11") (pinfunction "O_11") (pintype "output"))
      (node (ref "E17") (pin "10") (pinfunction "PRE_10") (pintype "input"))
    )
    (net (code "83") (name "Net-(E16D-O)") (class "Default")
      (node (ref "E16") (pin "8") (pinfunction "O_8") (pintype "output"))
      (node (ref "E21") (pin "11") (pinfunction "CLK_11") (pintype "input"))
    )
    (net (code "84") (name "Net-(E16E-I)") (class "Default")
      (node (ref "E16") (pin "11") (pinfunction "I_11") (pintype "input"))
      (node (ref "E3") (pin "11") (pinfunction "O_11") (pintype "output"))
      (node (ref "E3") (pin "2") (pinfunction "I1_2") (pintype "input"))
    )
    (net (code "85") (name "Net-(E16E-O)") (class "Default")
      (node (ref "E16") (pin "10") (pinfunction "O_10") (pintype "output"))
      (node (ref "E3") (pin "4") (pinfunction "I0_4") (pintype "input"))
    )
    (net (code "86") (name "Net-(E17A-CLK)") (class "Default")
      (node (ref "E17") (pin "3") (pinfunction "CLK_3") (pintype "input"))
      (node (ref "E9") (pin "8") (pinfunction "O_8") (pintype "output"))
    )
    (net (code "87") (name "Net-(E18A-I5)") (class "Default")
      (node (ref "E18") (pin "2") (pinfunction "I5_2") (pintype "input"))
      (node (ref "E18") (pin "3") (pinfunction "I6_3") (pintype "input"))
      (node (ref "E7") (pin "10") (pinfunction "O_10") (pintype "open_collector"))
      (node (ref "R12") (pin "1") (pinfunction "1_1") (pintype "passive"))
      (node (ref "R13") (pin "1") (pinfunction "1_1") (pintype "passive"))
    )
    (net (code "88") (name "Net-(E19B-O)") (class "Default")
      (node (ref "E19") (pin "6") (pinfunction "O_6") (pintype "output"))
      (node (ref "E21") (pin "3") (pinfunction "CLK_3") (pintype "input"))
    )
    (net (code "89") (name "Net-(E19C-O)") (class "Default")
      (node (ref "E19") (pin "8") (pinfunction "O_8") (pintype "output"))
      (node (ref "E2") (pin "11") (pinfunction "CLK_11") (pintype "input"))
      (node (ref "E2") (pin "3") (pinfunction "CLK_3") (pintype "input"))
      (node (ref "E8") (pin "11") (pinfunction "CLK_11") (pintype "input"))
      (node (ref "E8") (pin "3") (pinfunction "CLK_3") (pintype "input"))
    )
    (net (code "90") (name "Net-(E20A-I0)") (class "Default")
      (node (ref "DL1") (pin "3") (pinfunction "3_3") (pintype "passive"))
      (node (ref "E20") (pin "1") (pinfunction "I0_1") (pintype "input"))
      (node (ref "E20") (pin "2") (pinfunction "I1_2") (pintype "input"))
      (node (ref "R10") (pin "1") (pinfunction "1_1") (pintype "passive"))
    )
    (net (code "91") (name "Net-(E20B-O)") (class "Default")
      (node (ref "DL2") (pin "1") (pinfunction "1_1") (pintype "passive"))
      (node (ref "E20") (pin "6") (pinfunction "O_6") (pintype "output"))
      (node (ref "R9") (pin "1") (pinfunction "1_1") (pintype "passive"))
    )
    (net (code "92") (name "Net-(E20C-I0)") (class "Default")
      (node (ref "E20") (pin "10") (pinfunction "I1_10") (pintype "input"))
      (node (ref "E20") (pin "11") (pinfunction "O_11") (pintype "output"))
      (node (ref "E20") (pin "9") (pinfunction "I0_9") (pintype "input"))
    )
    (net (code "93") (name "Net-(E20D-I1)") (class "Default")
      (node (ref "DL2") (pin "3") (pinfunction "3_3") (pintype "passive"))
      (node (ref "E20") (pin "13") (pinfunction "I1_13") (pintype "input"))
      (node (ref "R8") (pin "1") (pinfunction "1_1") (pintype "passive"))
    )
    (net (code "94") (name "Net-(E22B-Q)") (class "Default")
      (node (ref "E22") (pin "9") (pinfunction "Q_9") (pintype "output"))
      (node (ref "E7") (pin "9") (pinfunction "I_9") (pintype "input"))
    )
    (net (code "95") (name "Net-(E23A-C)") (class "Default")
      (node (ref "C28") (pin "2") (pinfunction "2_2") (pintype "passive"))
      (node (ref "E23") (pin "14") (pinfunction "C_14") (pintype "input"))
    )
    (net (code "96") (name "Net-(E23A-Q)") (class "Default")
      (node (ref "E23") (pin "13") (pinfunction "Q_13") (pintype "output"))
      (node (ref "E23") (pin "9") (pinfunction "A_9") (pintype "input"))
    )
    (net (code "97") (name "Net-(E23A-R{slash}C)") (class "Default")
      (node (ref "C28") (pin "1") (pinfunction "1_1") (pintype "passive"))
      (node (ref "E23") (pin "15") (pinfunction "R/C_15") (pintype "input"))
      (node (ref "R6") (pin "1") (pinfunction "1_1") (pintype "passive"))
    )
    (net (code "98") (name "Net-(E23B-R{slash}C)") (class "Default")
      (node (ref "E23") (pin "7") (pinfunction "R/C_7") (pintype "input"))
      (node (ref "R7") (pin "1") (pinfunction "1_1") (pintype "passive"))
    )
    (net (code "99") (name "Net-(EDGEBF-1)") (class "Default")
      (node (ref "EDGE") (pin "BM2") (pinfunction "1_BM2") (pintype "bidirectional"))
      (node (ref "W2") (pin "2") (pinfunction "2_2") (pintype "passive"))
    )
    (net (code "100") (name "Net-(EDGEBJ-1)") (class "Default")
      (node (ref "EDGE") (pin "BP2") (pinfunction "1_BP2") (pintype "bidirectional"))
      (node (ref "W2") (pin "1") (pinfunction "1_1") (pintype "passive"))
    )
    (net (code "101") (name "Net-(Q1-B)") (class "Default")
      (node (ref "Q1") (pin "2") (pinfunction "B_2") (pintype "passive"))
      (node (ref "R12") (pin "2") (pinfunction "2_2") (pintype "passive"))
    )
    (net (code "102") (name "Net-(Q1-C)") (class "Default")
      (node (ref "Q1") (pin "3") (pinfunction "C_3") (pintype "passive"))
      (node (ref "R14") (pin "1") (pinfunction "1_1") (pintype "passive"))
    )
    (net (code "103") (name "VCC") (class "Default")
      (node (ref "C1") (pin "1") (pinfunction "1_1") (pintype "passive"))
      (node (ref "C10") (pin "1") (pinfunction "1_1") (pintype "passive"))
      (node (ref "C11") (pin "1") (pinfunction "1_1") (pintype "passive"))
      (node (ref "C12") (pin "1") (pinfunction "1_1") (pintype "passive"))
      (node (ref "C13") (pin "1") (pinfunction "1_1") (pintype "passive"))
      (node (ref "C14") (pin "1") (pinfunction "1_1") (pintype "passive"))
      (node (ref "C15") (pin "1") (pinfunction "1_1") (pintype "passive"))
      (node (ref "C16") (pin "1") (pinfunction "1_1") (pintype "passive"))
      (node (ref "C17") (pin "1") (pinfunction "1_1") (pintype "passive"))
      (node (ref "C18") (pin "1") (pinfunction "1_1") (pintype "passive"))
      (node (ref "C19") (pin "1") (pinfunction "1_1") (pintype "passive"))
      (node (ref "C2") (pin "1") (pinfunction "1_1") (pintype "passive"))
      (node (ref "C20") (pin "1") (pinfunction "1_1") (pintype "passive"))
      (node (ref "C21") (pin "1") (pinfunction "1_1") (pintype "passive"))
      (node (ref "C22") (pin "+") (pinfunction "+_+") (pintype "passive"))
      (node (ref "C23") (pin "+") (pinfunction "+_+") (pintype "passive"))
      (node (ref "C3") (pin "1") (pinfunction "1_1") (pintype "passive"))
      (node (ref "C4") (pin "1") (pinfunction "1_1") (pintype "passive"))
      (node (ref "C5") (pin "1") (pinfunction "1_1") (pintype "passive"))
      (node (ref "C6") (pin "1") (pinfunction "1_1") (pintype "passive"))
      (node (ref "C7") (pin "1") (pinfunction "1_1") (pintype "passive"))
      (node (ref "C8") (pin "1") (pinfunction "1_1") (pintype "passive"))
      (node (ref "C9") (pin "1") (pinfunction "1_1") (pintype "passive"))
      (node (ref "DL1") (pin "2") (pinfunction "2_2") (pintype "passive"))
      (node (ref "DL2") (pin "2") (pinfunction "2_2") (pintype "passive"))
      (node (ref "EDGE") (pin "AA2") (pinfunction "1_AA2") (pintype "bidirectional"))
      (node (ref "EDGE") (pin "BA2") (pinfunction "1_BA2") (pintype "bidirectional"))
      (node (ref "R1") (pin "2") (pinfunction "2_2") (pintype "passive"))
      (node (ref "R10") (pin "2") (pinfunction "2_2") (pintype "passive"))
      (node (ref "R11") (pin "2") (pinfunction "2_2") (pintype "passive"))
      (node (ref "R13") (pin "2") (pinfunction "2_2") (pintype "passive"))
      (node (ref "R14") (pin "2") (pinfunction "2_2") (pintype "passive"))
      (node (ref "R15") (pin "2") (pinfunction "2_2") (pintype "passive"))
      (node (ref "R16") (pin "2") (pinfunction "2_2") (pintype "passive"))
      (node (ref "R17") (pin "1") (pinfunction "1_1") (pintype "passive"))
      (node (ref "R18") (pin "2") (pinfunction "2_2") (pintype "passive"))
      (node (ref "R2") (pin "2") (pinfunction "2_2") (pintype "passive"))
      (node (ref "R4") (pin "2") (pinfunction "2_2") (pintype "passive"))
      (node (ref "R6") (pin "2") (pinfunction "2_2") (pintype "passive"))
      (node (ref "R7") (pin "2") (pinfunction "2_2") (pintype "passive"))
      (node (ref "R8") (pin "2") (pinfunction "2_2") (pintype "passive"))
      (node (ref "R9") (pin "2") (pinfunction "2_2") (pintype "passive"))
    )
    (net (code "104") (name "unconnected-(E2B-~{Q}-Pad8)") (class "Default")
      (node (ref "E2") (pin "8") (pinfunction "~{Q}_8") (pintype "output"))
    )
    (net (code "105") (name "unconnected-(E4A-O-Pad3)") (class "Default")
      (node (ref "E4") (pin "3") (pinfunction "O_3") (pintype "output"))
    )
    (net (code "106") (name "unconnected-(E4B-O-Pad6)") (class "Default")
      (node (ref "E4") (pin "6") (pinfunction "O_6") (pintype "output"))
    )
    (net (code "107") (name "unconnected-(E4D-O-Pad11)") (class "Default")
      (node (ref "E4") (pin "11") (pinfunction "O_11") (pintype "output"))
    )
    (net (code "108") (name "unconnected-(E5A-Q-Pad13)") (class "Default")
      (node (ref "E5") (pin "13") (pinfunction "Q_13") (pintype "output"))
    )
    (net (code "109") (name "unconnected-(E5B-~{Q}-Pad12)") (class "Default")
      (node (ref "E5") (pin "12") (pinfunction "~{Q}_12") (pintype "output"))
    )
    (net (code "110") (name "unconnected-(E6G-TAP1-Pad12)") (class "Default")
      (node (ref "E6") (pin "12") (pinfunction "TAP1_12") (pintype "output"))
    )
    (net (code "111") (name "unconnected-(E6G-TAP2-Pad4)") (class "Default")
      (node (ref "E6") (pin "4") (pinfunction "TAP2_4") (pintype "output"))
    )
    (net (code "112") (name "unconnected-(E6G-TAP3-Pad10)") (class "Default")
      (node (ref "E6") (pin "10") (pinfunction "TAP3_10") (pintype "output"))
    )
    (net (code "113") (name "unconnected-(E6G-TAP4-Pad6)") (class "Default")
      (node (ref "E6") (pin "6") (pinfunction "TAP4_6") (pintype "output"))
    )
    (net (code "114") (name "unconnected-(E8A-~{Q}-Pad6)") (class "Default")
      (node (ref "E8") (pin "6") (pinfunction "~{Q}_6") (pintype "output"))
    )
    (net (code "115") (name "unconnected-(E8B-~{Q}-Pad8)") (class "Default")
      (node (ref "E8") (pin "8") (pinfunction "~{Q}_8") (pintype "output"))
    )
    (net (code "116") (name "unconnected-(E11B-~{Q}-Pad12)") (class "Default")
      (node (ref "E11") (pin "12") (pinfunction "~{Q}_12") (pintype "output"))
    )
    (net (code "117") (name "unconnected-(E12A-I9-Pad12)") (class "Default")
      (node (ref "E12") (pin "12") (pinfunction "I9_12") (pintype "passive"))
    )
    (net (code "118") (name "unconnected-(E12A-I10-Pad11)") (class "Default")
      (node (ref "E12") (pin "11") (pinfunction "I10_11") (pintype "passive"))
    )
    (net (code "119") (name "unconnected-(E15C-O-Pad8)") (class "Default")
      (node (ref "E15") (pin "8") (pinfunction "O_8") (pintype "output"))
    )
    (net (code "120") (name "unconnected-(E18A-I9-Pad12)") (class "Default")
      (node (ref "E18") (pin "12") (pinfunction "I9_12") (pintype "passive"))
    )
    (net (code "121") (name "unconnected-(E18A-I10-Pad11)") (class "Default")
      (node (ref "E18") (pin "11") (pinfunction "I10_11") (pintype "passive"))
    )
    (net (code "122") (name "unconnected-(E19A-O-Pad12)") (class "Default")
      (node (ref "E19") (pin "12") (pinfunction "O_12") (pintype "output"))
    )
    (net (code "123") (name "unconnected-(E21A-~{Q}-Pad6)") (class "Default")
      (node (ref "E21") (pin "6") (pinfunction "~{Q}_6") (pintype "output"))
    )
    (net (code "124") (name "unconnected-(E21B-~{Q}-Pad8)") (class "Default")
      (node (ref "E21") (pin "8") (pinfunction "~{Q}_8") (pintype "output"))
    )
    (net (code "125") (name "unconnected-(E22A-~{Q}-Pad6)") (class "Default")
      (node (ref "E22") (pin "6") (pinfunction "~{Q}_6") (pintype "output"))
    )
    (net (code "126") (name "unconnected-(E22B-~{Q}-Pad8)") (class "Default")
      (node (ref "E22") (pin "8") (pinfunction "~{Q}_8") (pintype "output"))
    )
    (net (code "127") (name "unconnected-(E23A-~{Q}-Pad4)") (class "Default")
      (node (ref "E23") (pin "4") (pinfunction "~{Q}_4") (pintype "output"))
    )
    (net (code "128") (name "unconnected-(E23B-C-Pad6)") (class "Default")
      (node (ref "E23") (pin "6") (pinfunction "C_6") (pintype "input"))
    )
    (net (code "129") (name "unconnected-(E23B-~{Q}-Pad12)") (class "Default")
      (node (ref "E23") (pin "12") (pinfunction "~{Q}_12") (pintype "output"))
    )
  )
)
